# sensor.net
KiCad netlist of a schematic drawn in EAGLE
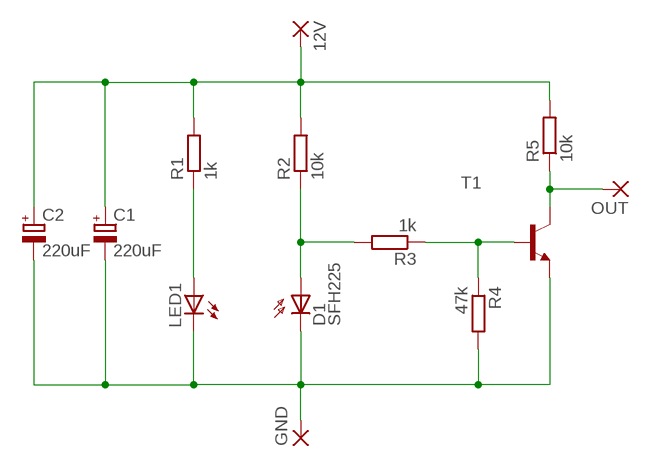
[diagram p0: schematic, sheet 1]

(export (version "E")
  (design (tool "Eeschema 10.0.6"))
  (components
    (comp (ref "12V")
      (value "SMD2")
      (footprint "eagle-import:SMD1,27-2,54")
      (libsource (lib "eagle-import") (part "SMD2"))
    )
    (comp (ref "C1")
      (value "220uF")
      (footprint "eagle-import:E5-6")
      (libsource (lib "eagle-import") (part "CPOL-EUE5-6"))
    )
    (comp (ref "C2")
      (value "220uF")
      (footprint "eagle-import:E5-6")
      (libsource (lib "eagle-import") (part "CPOL-EUE5-6"))
    )
    (comp (ref "D1")
      (value "SFH225")
      (footprint "eagle-import:SFH225")
      (libsource (lib "eagle-import") (part "SFH225"))
    )
    (comp (ref "GND")
      (value "SMD2")
      (footprint "eagle-import:SMD1,27-2,54")
      (libsource (lib "eagle-import") (part "SMD2"))
    )
    (comp (ref "LED1")
      (value "LED3MM")
      (footprint "eagle-import:LED3MM")
      (libsource (lib "eagle-import") (part "LED3MM"))
    )
    (comp (ref "OUT")
      (value "SMD2")
      (footprint "eagle-import:SMD1,27-2,54")
      (libsource (lib "eagle-import") (part "SMD2"))
    )
    (comp (ref "R1")
      (value "1k")
      (footprint "eagle-import:M0805")
      (libsource (lib "eagle-import") (part "R-EU_M0805"))
    )
    (comp (ref "R2")
      (value "10k")
      (footprint "eagle-import:M0805")
      (libsource (lib "eagle-import") (part "R-EU_M0805"))
    )
    (comp (ref "R3")
      (value "1k")
      (footprint "eagle-import:M0805")
      (libsource (lib "eagle-import") (part "R-EU_M0805"))
    )
    (comp (ref "R4")
      (value "47k")
      (footprint "eagle-import:M0805")
      (libsource (lib "eagle-import") (part "R-EU_M0805"))
    )
    (comp (ref "R5")
      (value "10k")
      (footprint "eagle-import:M0805")
      (libsource (lib "eagle-import") (part "R-EU_M0805"))
    )
    (comp (ref "T1")
      (value "-NPN-SOT23-EBC")
      (footprint "eagle-import:SOT23-EBC")
      (libsource (lib "eagle-import") (part "-NPN-SOT23-EBC"))
    )
  )
  (nets
    (net (code "1") (name "Net-(12V-P)") (class "Default")
      (node (ref "12V") (pin "1") (pinfunction "P_1") (pintype "passive"))
      (node (ref "C1") (pin "+") (pinfunction "+_+") (pintype "passive"))
      (node (ref "C2") (pin "+") (pinfunction "+_+") (pintype "passive"))
      (node (ref "R1") (pin "2") (pinfunction "2_2") (pintype "passive"))
      (node (ref "R2") (pin "2") (pinfunction "2_2") (pintype "passive"))
      (node (ref "R5") (pin "2") (pinfunction "2_2") (pintype "passive"))
    )
    (net (code "2") (name "Net-(D1-C)") (class "Default")
      (node (ref "C1") (pin "-") (pinfunction "-_-") (pintype "passive"))
      (node (ref "C2") (pin "-") (pinfunction "-_-") (pintype "passive"))
      (node (ref "D1") (pin "K") (pinfunction "C_K") (pintype "passive"))
      (node (ref "GND") (pin "1") (pinfunction "P_1") (pintype "passive"))
      (node (ref "LED1") (pin "K") (pinfunction "C_K") (pintype "passive"))
      (node (ref "R4") (pin "2") (pinfunction "2_2") (pintype "passive"))
      (node (ref "T1") (pin "E") (pinfunction "E_E") (pintype "passive"))
    )
    (net (code "3") (name "Net-(D1-PadA)") (class "Default")
      (node (ref "D1") (pin "A") (pinfunction "A_A") (pintype "passive"))
      (node (ref "R2") (pin "1") (pinfunction "1_1") (pintype "passive"))
      (node (ref "R3") (pin "2") (pinfunction "2_2") (pintype "passive"))
    )
    (net (code "4") (name "Net-(LED1-PadA)") (class "Default")
      (node (ref "LED1") (pin "A") (pinfunction "A_A") (pintype "passive"))
      (node (ref "R1") (pin "1") (pinfunction "1_1") (pintype "passive"))
    )
    (net (code "5") (name "Net-(OUT-P)") (class "Default")
      (node (ref "OUT") (pin "1") (pinfunction "P_1") (pintype "passive"))
      (node (ref "R5") (pin "1") (pinfunction "1_1") (pintype "passive"))
      (node (ref "T1") (pin "C") (pinfunction "C_C") (pintype "passive"))
    )
    (net (code "6") (name "Net-(R3-Pad1)") (class "Default")
      (node (ref "R3") (pin "1") (pinfunction "1_1") (pintype "passive"))
      (node (ref "R4") (pin "1") (pinfunction "1_1") (pintype "passive"))
      (node (ref "T1") (pin "B") (pinfunction "B_B") (pintype "passive"))
    )
  )
)
